# BMS_MAIN.net
KiCad netlist of a schematic drawn in Altium Designer
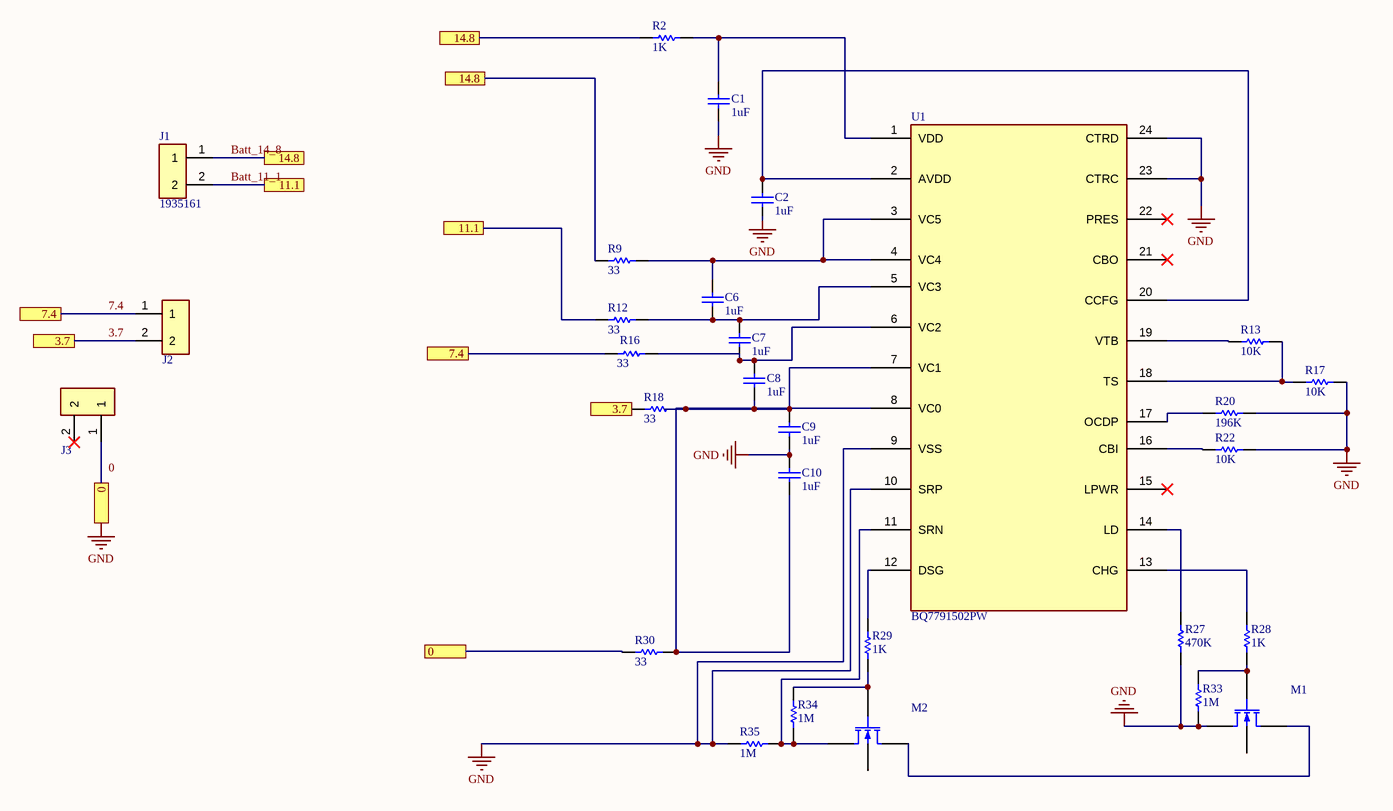
[diagram p0: BMS_MAIN.SchDoc]

(export (version "E")
  (design (tool "Eeschema 10.0.6"))
  (components
    (comp (ref "C1")
      (value "1uF")
      (footprint "0805")
      (description "Capacitor")
      (libsource (lib "Simulation Generic Components") (part "Capacitor"))
    )
    (comp (ref "C2")
      (value "1uF")
      (footprint "0805")
      (description "Capacitor")
      (libsource (lib "Simulation Generic Components") (part "Capacitor"))
    )
    (comp (ref "C6")
      (value "1uF")
      (footprint "0805")
      (description "Capacitor")
      (libsource (lib "Simulation Generic Components") (part "Capacitor"))
    )
    (comp (ref "C7")
      (value "1uF")
      (footprint "0805")
      (description "Capacitor")
      (libsource (lib "Simulation Generic Components") (part "Capacitor"))
    )
    (comp (ref "C8")
      (value "1uF")
      (footprint "0805")
      (description "Capacitor")
      (libsource (lib "Simulation Generic Components") (part "Capacitor"))
    )
    (comp (ref "C9")
      (value "1uF")
      (footprint "0805")
      (description "Capacitor")
      (libsource (lib "Simulation Generic Components") (part "Capacitor"))
    )
    (comp (ref "C10")
      (value "1uF")
      (footprint "0805")
      (description "Capacitor")
      (libsource (lib "Simulation Generic Components") (part "Capacitor"))
    )
    (comp (ref "J1")
      (value "1935161")
      (footprint "PHOENIX_1935161")
      (description "Conn Terminal Blocks 2 POS 5mm Solder ST Thru-Hole 16A")
      (fields (field (name "MF") "{'manufacturer': u'Phoenix Contact'}"))
      (libsource (lib "") (part "1935161_1"))
    )
    (comp (ref "J2")
      (value "1935161")
      (footprint "PHOENIX_1935161")
      (description "Conn Terminal Blocks 2 POS 5mm Solder ST Thru-Hole 16A")
      (fields (field (name "MF") "{'manufacturer': u'Phoenix Contact'}"))
      (libsource (lib "") (part "1935161_2"))
    )
    (comp (ref "J3")
      (value "1935161")
      (footprint "PHOENIX_1935161")
      (description "Conn Terminal Blocks 2 POS 5mm Solder ST Thru-Hole 16A")
      (fields (field (name "MF") "{'manufacturer': u'Phoenix Contact'}"))
      (libsource (lib "1935161") (part "1935161"))
    )
    (comp (ref "M1")
      (value "N-channel  MOS1 MOSFET Shichman and Hodges Model")
      (footprint "TO254P1036X470X1965-3")
      (libsource (lib "Simulation Generic Components") (part "MOSFET N-ch Lev1"))
    )
    (comp (ref "M2")
      (value "N-channel  MOS1 MOSFET Shichman and Hodges Model")
      (footprint "TO254P1036X470X1965-3")
      (libsource (lib "Simulation Generic Components") (part "MOSFET N-ch Lev1"))
    )
    (comp (ref "R2")
      (value "1K")
      (footprint "0805")
      (description "Resistor")
      (libsource (lib "Simulation Generic Components") (part "Resistor"))
    )
    (comp (ref "R9")
      (value "33")
      (footprint "0805")
      (description "Resistor")
      (libsource (lib "Simulation Generic Components") (part "Resistor"))
    )
    (comp (ref "R12")
      (value "33")
      (footprint "0805")
      (description "Resistor")
      (libsource (lib "Simulation Generic Components") (part "Resistor"))
    )
    (comp (ref "R13")
      (value "10K")
      (footprint "0805")
      (description "Resistor")
      (libsource (lib "Simulation Generic Components") (part "Resistor"))
    )
    (comp (ref "R16")
      (value "33")
      (footprint "0805")
      (description "Resistor")
      (libsource (lib "Simulation Generic Components") (part "Resistor"))
    )
    (comp (ref "R17")
      (value "10K")
      (footprint "0805")
      (description "Resistor")
      (libsource (lib "Simulation Generic Components") (part "Resistor"))
    )
    (comp (ref "R18")
      (value "33")
      (footprint "0805")
      (description "Resistor")
      (libsource (lib "Simulation Generic Components") (part "Resistor"))
    )
    (comp (ref "R20")
      (value "196K")
      (footprint "0805")
      (description "Resistor")
      (libsource (lib "Simulation Generic Components") (part "Resistor"))
    )
    (comp (ref "R22")
      (value "10K")
      (footprint "0805")
      (description "Resistor")
      (libsource (lib "Simulation Generic Components") (part "Resistor"))
    )
    (comp (ref "R27")
      (value "470K")
      (footprint "0805")
      (description "Resistor")
      (libsource (lib "Simulation Generic Components") (part "Resistor"))
    )
    (comp (ref "R28")
      (value "1K")
      (footprint "0805")
      (description "Resistor")
      (libsource (lib "Simulation Generic Components") (part "Resistor"))
    )
    (comp (ref "R29")
      (value "1K")
      (footprint "0805")
      (description "Resistor")
      (libsource (lib "Simulation Generic Components") (part "Resistor"))
    )
    (comp (ref "R30")
      (value "33")
      (footprint "0805")
      (description "Resistor")
      (libsource (lib "Simulation Generic Components") (part "Resistor"))
    )
    (comp (ref "R33")
      (value "1M")
      (footprint "0805")
      (description "Resistor")
      (libsource (lib "Simulation Generic Components") (part "Resistor"))
    )
    (comp (ref "R34")
      (value "1M")
      (footprint "0805")
      (description "Resistor")
      (libsource (lib "Simulation Generic Components") (part "Resistor"))
    )
    (comp (ref "R35")
      (value "1M")
      (footprint "0805")
      (description "Resistor")
      (libsource (lib "Simulation Generic Components") (part "Resistor"))
    )
    (comp (ref "U1")
      (value "BQ7791502PW")
      (footprint "SOP65P640X120-24N")
      (libsource (lib "BQ7791502PW") (part "BQ7791502PW"))
    )
  )
  (nets
    (net (code "1") (name "/3.7") (class "Default")
      (node (ref "J2") (pin "2") (pinfunction "2_2") (pintype "passive"))
      (node (ref "R18") (pin "2") (pinfunction "2_2") (pintype "passive"))
    )
    (net (code "2") (name "/7.4") (class "Default")
      (node (ref "J2") (pin "1") (pinfunction "1_1") (pintype "passive"))
      (node (ref "R16") (pin "2") (pinfunction "2_2") (pintype "passive"))
    )
    (net (code "3") (name "/Batt_11_1") (class "Default")
      (node (ref "J1") (pin "2") (pinfunction "2_2") (pintype "passive"))
      (node (ref "R12") (pin "2") (pinfunction "2_2") (pintype "passive"))
    )
    (net (code "4") (name "/Batt_14_8") (class "Default")
      (node (ref "J1") (pin "1") (pinfunction "1_1") (pintype "passive"))
      (node (ref "R2") (pin "2") (pinfunction "2_2") (pintype "passive"))
      (node (ref "R9") (pin "2") (pinfunction "2_2") (pintype "passive"))
    )
    (net (code "5") (name "GND") (class "Default")
      (node (ref "C1") (pin "1") (pinfunction "1_1") (pintype "passive"))
      (node (ref "C10") (pin "1") (pinfunction "1_1") (pintype "passive"))
      (node (ref "C2") (pin "2") (pinfunction "2_2") (pintype "passive"))
      (node (ref "C9") (pin "2") (pinfunction "2_2") (pintype "passive"))
      (node (ref "J3") (pin "1") (pinfunction "1_1") (pintype "passive"))
      (node (ref "M1") (pin "3") (pinfunction "S_3") (pintype "passive"))
      (node (ref "R17") (pin "1") (pinfunction "1_1") (pintype "passive"))
      (node (ref "R20") (pin "2") (pinfunction "2_2") (pintype "passive"))
      (node (ref "R22") (pin "2") (pinfunction "2_2") (pintype "passive"))
      (node (ref "R27") (pin "1") (pinfunction "1_1") (pintype "passive"))
      (node (ref "R30") (pin "2") (pinfunction "2_2") (pintype "passive"))
      (node (ref "R33") (pin "1") (pinfunction "1_1") (pintype "passive"))
      (node (ref "R35") (pin "2") (pinfunction "2_2") (pintype "passive"))
      (node (ref "U1") (pin "10") (pinfunction "SRP_10") (pintype "passive"))
      (node (ref "U1") (pin "23") (pinfunction "CTRC_23") (pintype "passive"))
      (node (ref "U1") (pin "24") (pinfunction "CTRD_24") (pintype "passive"))
      (node (ref "U1") (pin "9") (pinfunction "VSS_9") (pintype "passive"))
    )
    (net (code "6") (name "Net-(M1-D)") (class "Default")
      (node (ref "M1") (pin "1") (pinfunction "D_1") (pintype "passive"))
      (node (ref "M2") (pin "1") (pinfunction "D_1") (pintype "passive"))
    )
    (net (code "7") (name "Net-(M1-G)") (class "Default")
      (node (ref "M1") (pin "2") (pinfunction "G_2") (pintype "passive"))
      (node (ref "R28") (pin "1") (pinfunction "1_1") (pintype "passive"))
      (node (ref "R33") (pin "2") (pinfunction "2_2") (pintype "passive"))
    )
    (net (code "8") (name "Net-(M2-G)") (class "Default")
      (node (ref "M2") (pin "2") (pinfunction "G_2") (pintype "passive"))
      (node (ref "R29") (pin "1") (pinfunction "1_1") (pintype "passive"))
      (node (ref "R34") (pin "2") (pinfunction "2_2") (pintype "passive"))
    )
    (net (code "9") (name "Net-(M2-S)") (class "Default")
      (node (ref "M2") (pin "3") (pinfunction "S_3") (pintype "passive"))
      (node (ref "R34") (pin "1") (pinfunction "1_1") (pintype "passive"))
      (node (ref "R35") (pin "1") (pinfunction "1_1") (pintype "passive"))
      (node (ref "U1") (pin "11") (pinfunction "SRN_11") (pintype "passive"))
    )
    (net (code "10") (name "Net-(U1-AVDD)") (class "Default")
      (node (ref "C2") (pin "1") (pinfunction "1_1") (pintype "passive"))
      (node (ref "U1") (pin "2") (pinfunction "AVDD_2") (pintype "passive"))
      (node (ref "U1") (pin "20") (pinfunction "CCFG_20") (pintype "passive"))
    )
    (net (code "11") (name "Net-(U1-CBI)") (class "Default")
      (node (ref "R22") (pin "1") (pinfunction "1_1") (pintype "passive"))
      (node (ref "U1") (pin "16") (pinfunction "CBI_16") (pintype "passive"))
    )
    (net (code "12") (name "Net-(U1-CHG)") (class "Default")
      (node (ref "R28") (pin "2") (pinfunction "2_2") (pintype "passive"))
      (node (ref "U1") (pin "13") (pinfunction "CHG_13") (pintype "passive"))
    )
    (net (code "13") (name "Net-(U1-DSG)") (class "Default")
      (node (ref "R29") (pin "2") (pinfunction "2_2") (pintype "passive"))
      (node (ref "U1") (pin "12") (pinfunction "DSG_12") (pintype "passive"))
    )
    (net (code "14") (name "Net-(U1-LD)") (class "Default")
      (node (ref "R27") (pin "2") (pinfunction "2_2") (pintype "passive"))
      (node (ref "U1") (pin "14") (pinfunction "LD_14") (pintype "passive"))
    )
    (net (code "15") (name "Net-(U1-OCDP)") (class "Default")
      (node (ref "R20") (pin "1") (pinfunction "1_1") (pintype "passive"))
      (node (ref "U1") (pin "17") (pinfunction "OCDP_17") (pintype "passive"))
    )
    (net (code "16") (name "Net-(U1-TS)") (class "Default")
      (node (ref "R13") (pin "2") (pinfunction "2_2") (pintype "passive"))
      (node (ref "R17") (pin "2") (pinfunction "2_2") (pintype "passive"))
      (node (ref "U1") (pin "18") (pinfunction "TS_18") (pintype "passive"))
    )
    (net (code "17") (name "Net-(U1-VC0)") (class "Default")
      (node (ref "C10") (pin "2") (pinfunction "2_2") (pintype "passive"))
      (node (ref "R30") (pin "1") (pinfunction "1_1") (pintype "passive"))
      (node (ref "U1") (pin "8") (pinfunction "VC0_8") (pintype "passive"))
    )
    (net (code "18") (name "Net-(U1-VC1)") (class "Default")
      (node (ref "C8") (pin "2") (pinfunction "2_2") (pintype "passive"))
      (node (ref "C9") (pin "1") (pinfunction "1_1") (pintype "passive"))
      (node (ref "R18") (pin "1") (pinfunction "1_1") (pintype "passive"))
      (node (ref "U1") (pin "7") (pinfunction "VC1_7") (pintype "passive"))
    )
    (net (code "19") (name "Net-(U1-VC2)") (class "Default")
      (node (ref "C7") (pin "2") (pinfunction "2_2") (pintype "passive"))
      (node (ref "C8") (pin "1") (pinfunction "1_1") (pintype "passive"))
      (node (ref "R16") (pin "1") (pinfunction "1_1") (pintype "passive"))
      (node (ref "U1") (pin "6") (pinfunction "VC2_6") (pintype "passive"))
    )
    (net (code "20") (name "Net-(U1-VC3)") (class "Default")
      (node (ref "C6") (pin "2") (pinfunction "2_2") (pintype "passive"))
      (node (ref "C7") (pin "1") (pinfunction "1_1") (pintype "passive"))
      (node (ref "R12") (pin "1") (pinfunction "1_1") (pintype "passive"))
      (node (ref "U1") (pin "5") (pinfunction "VC3_5") (pintype "passive"))
    )
    (net (code "21") (name "Net-(U1-VC4)") (class "Default")
      (node (ref "C6") (pin "1") (pinfunction "1_1") (pintype "passive"))
      (node (ref "R9") (pin "1") (pinfunction "1_1") (pintype "passive"))
      (node (ref "U1") (pin "3") (pinfunction "VC5_3") (pintype "passive"))
      (node (ref "U1") (pin "4") (pinfunction "VC4_4") (pintype "passive"))
    )
    (net (code "22") (name "Net-(U1-VDD)") (class "Default")
      (node (ref "C1") (pin "2") (pinfunction "2_2") (pintype "passive"))
      (node (ref "R2") (pin "1") (pinfunction "1_1") (pintype "passive"))
      (node (ref "U1") (pin "1") (pinfunction "VDD_1") (pintype "passive"))
    )
    (net (code "23") (name "Net-(U1-VTB)") (class "Default")
      (node (ref "R13") (pin "1") (pinfunction "1_1") (pintype "passive"))
      (node (ref "U1") (pin "19") (pinfunction "VTB_19") (pintype "passive"))
    )
    (net (code "24") (name "unconnected-(J3-Pad2)") (class "Default")
      (node (ref "J3") (pin "2") (pinfunction "2_2") (pintype "passive+no_connect"))
    )
    (net (code "25") (name "unconnected-(M1-B-Pad4)") (class "Default")
      (node (ref "M1") (pin "4") (pinfunction "B_4") (pintype "passive"))
    )
    (net (code "26") (name "unconnected-(M2-B-Pad4)") (class "Default")
      (node (ref "M2") (pin "4") (pinfunction "B_4") (pintype "passive"))
    )
    (net (code "27") (name "unconnected-(U1-CBO-Pad21)") (class "Default")
      (node (ref "U1") (pin "21") (pinfunction "CBO_21") (pintype "passive+no_connect"))
    )
    (net (code "28") (name "unconnected-(U1-LPWR-Pad15)") (class "Default")
      (node (ref "U1") (pin "15") (pinfunction "LPWR_15") (pintype "passive+no_connect"))
    )
    (net (code "29") (name "unconnected-(U1-PRES-Pad22)") (class "Default")
      (node (ref "U1") (pin "22") (pinfunction "PRES_22") (pintype "passive+no_connect"))
    )
  )
)
